# CtDPS_Stage.net
KiCad netlist of a schematic drawn in Altium Designer
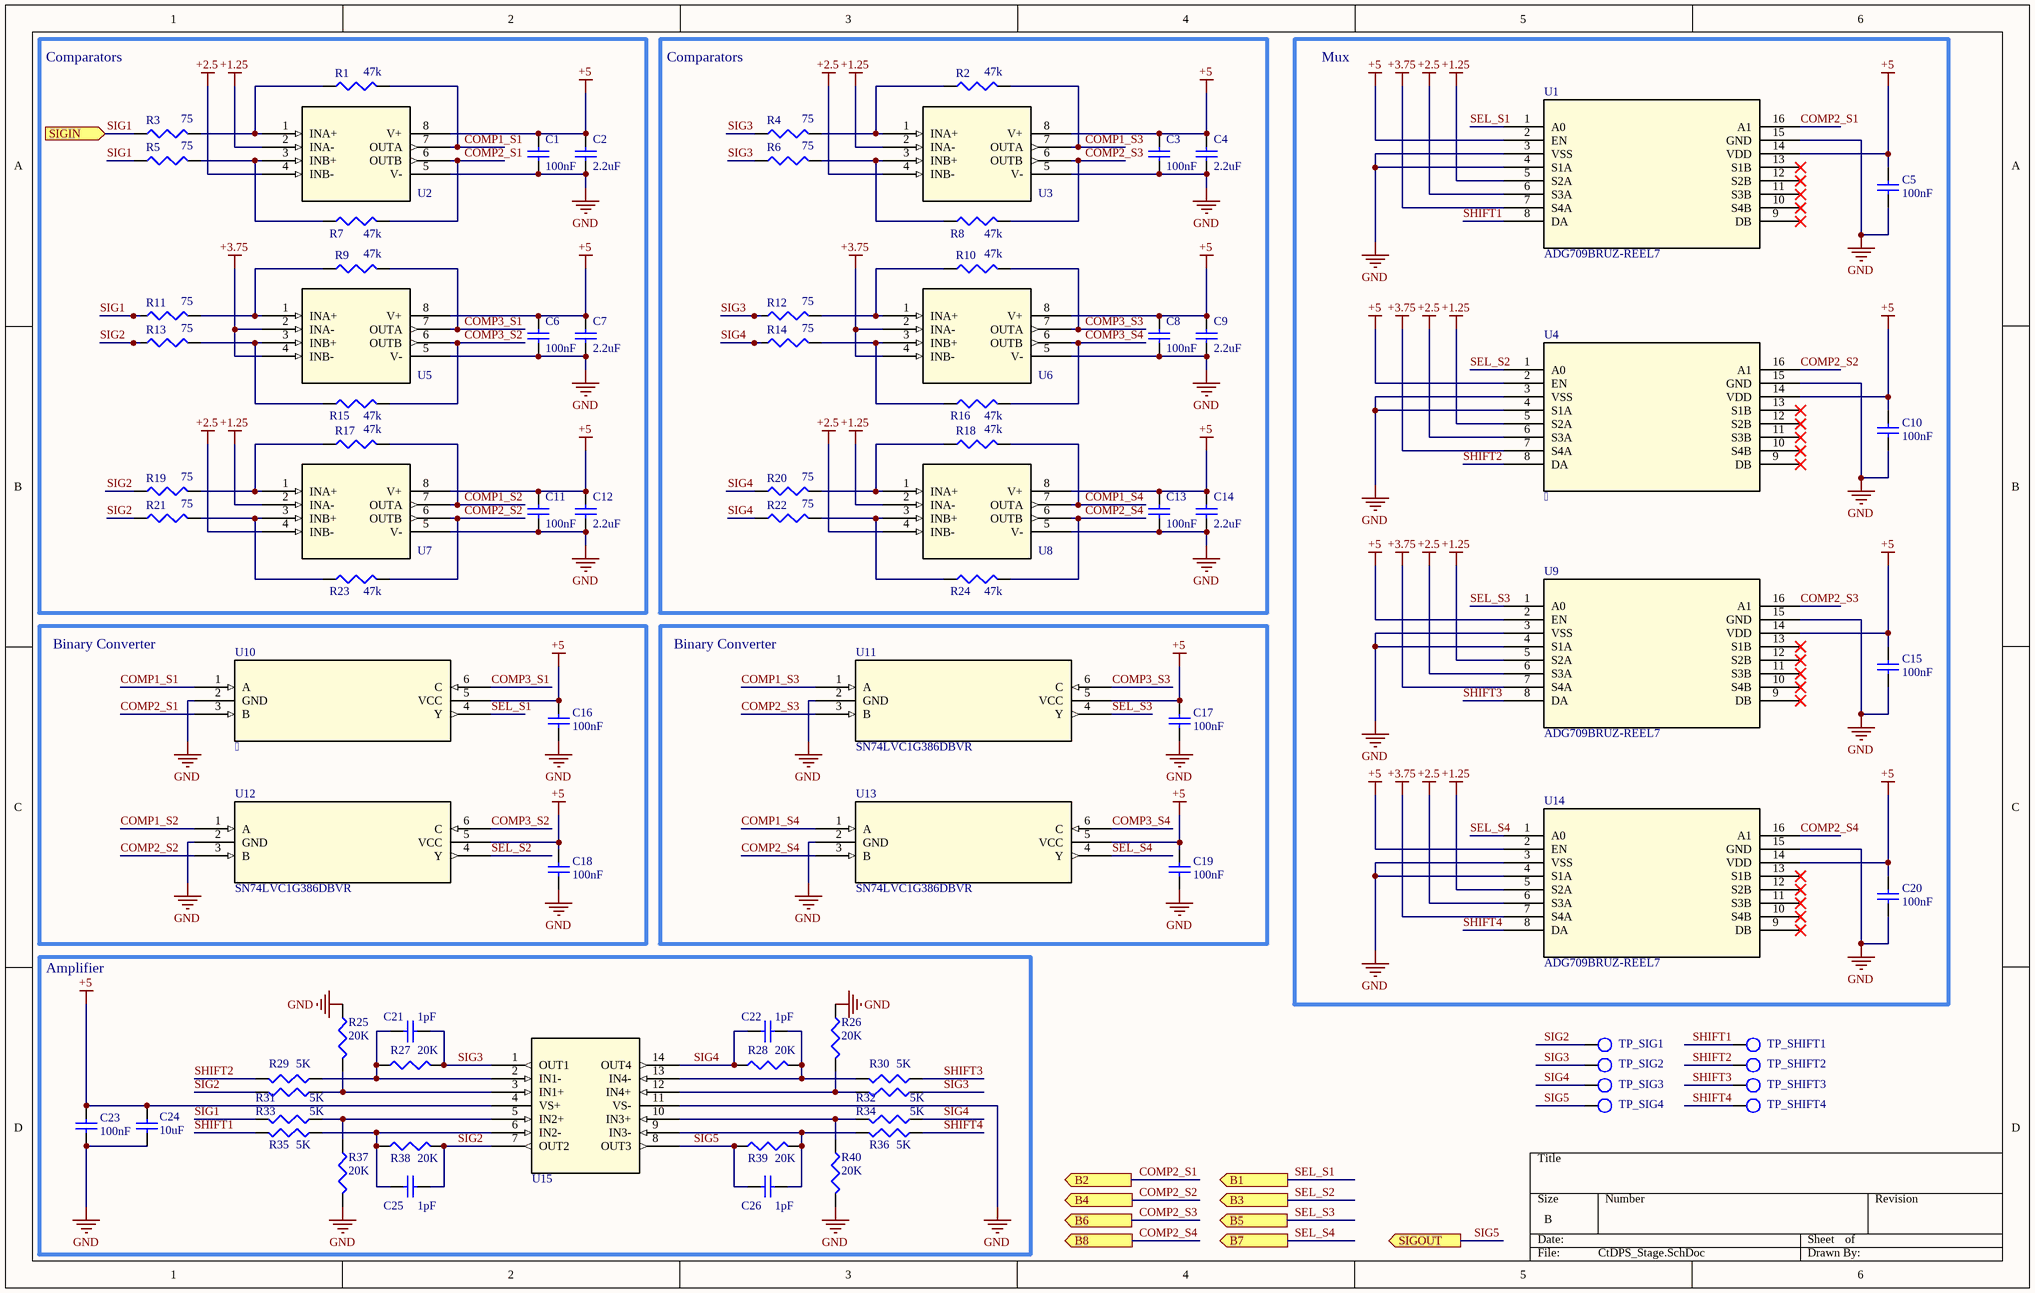
[diagram p0: CtDPS_Stage.SchDoc]

(export (version "E")
  (design (tool "Eeschema 10.0.6"))
  (components
    (comp (ref "C1")
      (value "100nF")
      (footprint "C_0402")
      (fields (field (name "LCSC PART #") "C1525"))
      (libsource (lib "ctdsp") (part "C_0402"))
    )
    (comp (ref "C2")
      (value "2.2uF")
      (footprint "C_0402")
      (fields (field (name "LCSC PART #") "C12530"))
      (libsource (lib "ctdsp") (part "C_0402"))
    )
    (comp (ref "C3")
      (value "100nF")
      (footprint "C_0402")
      (fields (field (name "LCSC PART #") "C1525"))
      (libsource (lib "ctdsp") (part "C_0402"))
    )
    (comp (ref "C4")
      (value "2.2uF")
      (footprint "C_0402")
      (fields (field (name "LCSC PART #") "C12530"))
      (libsource (lib "ctdsp") (part "C_0402"))
    )
    (comp (ref "C5")
      (value "100nF")
      (footprint "C_0402")
      (fields (field (name "LCSC PART #") "C1525"))
      (libsource (lib "ctdsp") (part "C_0402"))
    )
    (comp (ref "C6")
      (value "100nF")
      (footprint "C_0402")
      (fields (field (name "LCSC PART #") "C1525"))
      (libsource (lib "ctdsp") (part "C_0402"))
    )
    (comp (ref "C7")
      (value "2.2uF")
      (footprint "C_0402")
      (fields (field (name "LCSC PART #") "C12530"))
      (libsource (lib "ctdsp") (part "C_0402"))
    )
    (comp (ref "C8")
      (value "100nF")
      (footprint "C_0402")
      (fields (field (name "LCSC PART #") "C1525"))
      (libsource (lib "ctdsp") (part "C_0402"))
    )
    (comp (ref "C9")
      (value "2.2uF")
      (footprint "C_0402")
      (fields (field (name "LCSC PART #") "C12530"))
      (libsource (lib "ctdsp") (part "C_0402"))
    )
    (comp (ref "C10")
      (value "100nF")
      (footprint "C_0402")
      (fields (field (name "LCSC PART #") "C1525"))
      (libsource (lib "ctdsp") (part "C_0402"))
    )
    (comp (ref "C11")
      (value "100nF")
      (footprint "C_0402")
      (fields (field (name "LCSC PART #") "C1525"))
      (libsource (lib "ctdsp") (part "C_0402"))
    )
    (comp (ref "C12")
      (value "2.2uF")
      (footprint "C_0402")
      (fields (field (name "LCSC PART #") "C12530"))
      (libsource (lib "ctdsp") (part "C_0402"))
    )
    (comp (ref "C13")
      (value "100nF")
      (footprint "C_0402")
      (fields (field (name "LCSC PART #") "C1525"))
      (libsource (lib "ctdsp") (part "C_0402"))
    )
    (comp (ref "C14")
      (value "2.2uF")
      (footprint "C_0402")
      (fields (field (name "LCSC PART #") "C12530"))
      (libsource (lib "ctdsp") (part "C_0402"))
    )
    (comp (ref "C15")
      (value "100nF")
      (footprint "C_0402")
      (fields (field (name "LCSC PART #") "C1525"))
      (libsource (lib "ctdsp") (part "C_0402"))
    )
    (comp (ref "C16")
      (value "100nF")
      (footprint "C_0402")
      (fields (field (name "LCSC PART #") "C1525"))
      (libsource (lib "ctdsp") (part "C_0402"))
    )
    (comp (ref "C17")
      (value "100nF")
      (footprint "C_0402")
      (fields (field (name "LCSC PART #") "C1525"))
      (libsource (lib "ctdsp") (part "C_0402"))
    )
    (comp (ref "C18")
      (value "100nF")
      (footprint "C_0402")
      (fields (field (name "LCSC PART #") "C1525"))
      (libsource (lib "ctdsp") (part "C_0402"))
    )
    (comp (ref "C19")
      (value "100nF")
      (footprint "C_0402")
      (fields (field (name "LCSC PART #") "C1525"))
      (libsource (lib "ctdsp") (part "C_0402"))
    )
    (comp (ref "C20")
      (value "100nF")
      (footprint "C_0402")
      (fields (field (name "LCSC PART #") "C1525"))
      (libsource (lib "ctdsp") (part "C_0402"))
    )
    (comp (ref "C21")
      (value "1pF")
      (footprint "C_0402")
      (fields (field (name "LCSC PART #") "C1550"))
      (libsource (lib "ctdsp") (part "C_0402"))
    )
    (comp (ref "C22")
      (value "1pF")
      (footprint "C_0402")
      (fields (field (name "LCSC PART #") "C1550"))
      (libsource (lib "ctdsp") (part "C_0402"))
    )
    (comp (ref "C23")
      (value "100nF")
      (footprint "C_0402")
      (fields (field (name "LCSC PART #") "C1525"))
      (libsource (lib "ctdsp") (part "C_0402"))
    )
    (comp (ref "C24")
      (value "10uF")
      (footprint "C_0402")
      (fields (field (name "LCSC PART #") "C15525"))
      (libsource (lib "ctdsp") (part "C_0402"))
    )
    (comp (ref "C25")
      (value "1pF")
      (footprint "C_0402")
      (fields (field (name "LCSC PART #") "C1550"))
      (libsource (lib "ctdsp") (part "C_0402"))
    )
    (comp (ref "C26")
      (value "1pF")
      (footprint "C_0402")
      (fields (field (name "LCSC PART #") "C1550"))
      (libsource (lib "ctdsp") (part "C_0402"))
    )
    (comp (ref "R1")
      (value "47k")
      (footprint "RES_0603")
      (fields (field (name "LCSC PART #") "C25819"))
      (libsource (lib "ctdsp") (part "RES_0603"))
    )
    (comp (ref "R2")
      (value "47k")
      (footprint "RES_0603")
      (fields (field (name "LCSC PART #") "C25819"))
      (libsource (lib "ctdsp") (part "RES_0603"))
    )
    (comp (ref "R3")
      (value "75")
      (footprint "RES_0603")
      (fields (field (name "LCSC PART #") "C4275"))
      (libsource (lib "ctdsp") (part "RES_0603"))
    )
    (comp (ref "R4")
      (value "75")
      (footprint "RES_0603")
      (fields (field (name "LCSC PART #") "C4275"))
      (libsource (lib "ctdsp") (part "RES_0603"))
    )
    (comp (ref "R5")
      (value "75")
      (footprint "RES_0603")
      (fields (field (name "LCSC PART #") "C4275"))
      (libsource (lib "ctdsp") (part "RES_0603"))
    )
    (comp (ref "R6")
      (value "75")
      (footprint "RES_0603")
      (fields (field (name "LCSC PART #") "C4275"))
      (libsource (lib "ctdsp") (part "RES_0603"))
    )
    (comp (ref "R7")
      (value "47k")
      (footprint "RES_0603")
      (fields (field (name "LCSC PART #") "C25819"))
      (libsource (lib "ctdsp") (part "RES_0603"))
    )
    (comp (ref "R8")
      (value "47k")
      (footprint "RES_0603")
      (fields (field (name "LCSC PART #") "C25819"))
      (libsource (lib "ctdsp") (part "RES_0603"))
    )
    (comp (ref "R9")
      (value "47k")
      (footprint "RES_0603")
      (fields (field (name "LCSC PART #") "C25819"))
      (libsource (lib "ctdsp") (part "RES_0603"))
    )
    (comp (ref "R10")
      (value "47k")
      (footprint "RES_0603")
      (fields (field (name "LCSC PART #") "C25819"))
      (libsource (lib "ctdsp") (part "RES_0603"))
    )
    (comp (ref "R11")
      (value "75")
      (footprint "RES_0603")
      (fields (field (name "LCSC PART #") "C4275"))
      (libsource (lib "ctdsp") (part "RES_0603"))
    )
    (comp (ref "R12")
      (value "75")
      (footprint "RES_0603")
      (fields (field (name "LCSC PART #") "C4275"))
      (libsource (lib "ctdsp") (part "RES_0603"))
    )
    (comp (ref "R13")
      (value "75")
      (footprint "RES_0603")
      (fields (field (name "LCSC PART #") "C4275"))
      (libsource (lib "ctdsp") (part "RES_0603"))
    )
    (comp (ref "R14")
      (value "75")
      (footprint "RES_0603")
      (fields (field (name "LCSC PART #") "C4275"))
      (libsource (lib "ctdsp") (part "RES_0603"))
    )
    (comp (ref "R15")
      (value "47k")
      (footprint "RES_0603")
      (fields (field (name "LCSC PART #") "C25819"))
      (libsource (lib "ctdsp") (part "RES_0603"))
    )
    (comp (ref "R16")
      (value "47k")
      (footprint "RES_0603")
      (fields (field (name "LCSC PART #") "C25819"))
      (libsource (lib "ctdsp") (part "RES_0603"))
    )
    (comp (ref "R17")
      (value "47k")
      (footprint "RES_0603")
      (fields (field (name "LCSC PART #") "C25819"))
      (libsource (lib "ctdsp") (part "RES_0603"))
    )
    (comp (ref "R18")
      (value "47k")
      (footprint "RES_0603")
      (fields (field (name "LCSC PART #") "C25819"))
      (libsource (lib "ctdsp") (part "RES_0603"))
    )
    (comp (ref "R19")
      (value "75")
      (footprint "RES_0603")
      (fields (field (name "LCSC PART #") "C4275"))
      (libsource (lib "ctdsp") (part "RES_0603"))
    )
    (comp (ref "R20")
      (value "75")
      (footprint "RES_0603")
      (fields (field (name "LCSC PART #") "C4275"))
      (libsource (lib "ctdsp") (part "RES_0603"))
    )
    (comp (ref "R21")
      (value "75")
      (footprint "RES_0603")
      (fields (field (name "LCSC PART #") "C4275"))
      (libsource (lib "ctdsp") (part "RES_0603"))
    )
    (comp (ref "R22")
      (value "75")
      (footprint "RES_0603")
      (fields (field (name "LCSC PART #") "C4275"))
      (libsource (lib "ctdsp") (part "RES_0603"))
    )
    (comp (ref "R23")
      (value "47k")
      (footprint "RES_0603")
      (fields (field (name "LCSC PART #") "C25819"))
      (libsource (lib "ctdsp") (part "RES_0603"))
    )
    (comp (ref "R24")
      (value "47k")
      (footprint "RES_0603")
      (fields (field (name "LCSC PART #") "C25819"))
      (libsource (lib "ctdsp") (part "RES_0603"))
    )
    (comp (ref "R25")
      (value "20K")
      (footprint "RES_0402")
      (fields (field (name "LCSC PART #") "C25765"))
      (libsource (lib "ctdsp") (part "RES_0402"))
    )
    (comp (ref "R26")
      (value "20K")
      (footprint "RES_0402")
      (fields (field (name "LCSC PART #") "C25765"))
      (libsource (lib "ctdsp") (part "RES_0402"))
    )
    (comp (ref "R27")
      (value "20K")
      (footprint "RES_0402")
      (fields (field (name "LCSC PART #") "C25765"))
      (libsource (lib "ctdsp") (part "RES_0402"))
    )
    (comp (ref "R28")
      (value "20K")
      (footprint "RES_0402")
      (fields (field (name "LCSC PART #") "C25765"))
      (libsource (lib "ctdsp") (part "RES_0402"))
    )
    (comp (ref "R29")
      (value "5K")
      (footprint "RES_0402")
      (fields (field (name "LCSC PART #") "C5948099"))
      (libsource (lib "ctdsp") (part "RES_0402"))
    )
    (comp (ref "R30")
      (value "5K")
      (footprint "RES_0402")
      (fields (field (name "LCSC PART #") "C5948099"))
      (libsource (lib "ctdsp") (part "RES_0402"))
    )
    (comp (ref "R31")
      (value "5K")
      (footprint "RES_0402")
      (fields (field (name "LCSC PART #") "C5948099"))
      (libsource (lib "ctdsp") (part "RES_0402"))
    )
    (comp (ref "R32")
      (value "5K")
      (footprint "RES_0402")
      (fields (field (name "LCSC PART #") "C5948099"))
      (libsource (lib "ctdsp") (part "RES_0402"))
    )
    (comp (ref "R33")
      (value "5K")
      (footprint "RES_0402")
      (fields (field (name "LCSC PART #") "C5948099"))
      (libsource (lib "ctdsp") (part "RES_0402"))
    )
    (comp (ref "R34")
      (value "5K")
      (footprint "RES_0402")
      (fields (field (name "LCSC PART #") "C5948099"))
      (libsource (lib "ctdsp") (part "RES_0402"))
    )
    (comp (ref "R35")
      (value "5K")
      (footprint "RES_0402")
      (fields (field (name "LCSC PART #") "C5948099"))
      (libsource (lib "ctdsp") (part "RES_0402"))
    )
    (comp (ref "R36")
      (value "5K")
      (footprint "RES_0402")
      (fields (field (name "LCSC PART #") "C5948099"))
      (libsource (lib "ctdsp") (part "RES_0402"))
    )
    (comp (ref "R37")
      (value "20K")
      (footprint "RES_0402")
      (fields (field (name "LCSC PART #") "C25765"))
      (libsource (lib "ctdsp") (part "RES_0402"))
    )
    (comp (ref "R38")
      (value "20K")
      (footprint "RES_0402")
      (fields (field (name "LCSC PART #") "C25765"))
      (libsource (lib "ctdsp") (part "RES_0402"))
    )
    (comp (ref "R39")
      (value "20K")
      (footprint "RES_0402")
      (fields (field (name "LCSC PART #") "C25765"))
      (libsource (lib "ctdsp") (part "RES_0402"))
    )
    (comp (ref "R40")
      (value "20K")
      (footprint "RES_0402")
      (fields (field (name "LCSC PART #") "C25765"))
      (libsource (lib "ctdsp") (part "RES_0402"))
    )
    (comp (ref "TP_SHIFT1")
      (value "TESTPOINT")
      (footprint "TESTPOINT")
      (libsource (lib "ctdsp") (part "TESTPOINT"))
    )
    (comp (ref "TP_SHIFT2")
      (value "TESTPOINT")
      (footprint "TESTPOINT")
      (libsource (lib "ctdsp") (part "TESTPOINT"))
    )
    (comp (ref "TP_SHIFT3")
      (value "TESTPOINT")
      (footprint "TESTPOINT")
      (libsource (lib "ctdsp") (part "TESTPOINT"))
    )
    (comp (ref "TP_SHIFT4")
      (value "TESTPOINT")
      (footprint "TESTPOINT")
      (libsource (lib "ctdsp") (part "TESTPOINT"))
    )
    (comp (ref "TP_SIG1")
      (value "TESTPOINT")
      (footprint "TESTPOINT")
      (libsource (lib "ctdsp") (part "TESTPOINT"))
    )
    (comp (ref "TP_SIG2")
      (value "TESTPOINT")
      (footprint "TESTPOINT")
      (libsource (lib "ctdsp") (part "TESTPOINT"))
    )
    (comp (ref "TP_SIG3")
      (value "TESTPOINT")
      (footprint "TESTPOINT")
      (libsource (lib "ctdsp") (part "TESTPOINT"))
    )
    (comp (ref "TP_SIG4")
      (value "TESTPOINT")
      (footprint "TESTPOINT")
      (libsource (lib "ctdsp") (part "TESTPOINT"))
    )
    (comp (ref "U1")
      (value "ADG709BRUZ-REEL7")
      (footprint "ADG709BRUZ-REEL7")
      (description "CMOS Low Voltage, 3 Î© 4-Channel Multiplexer")
      (fields (field (name "LCSC PART #") "C206785"))
      (libsource (lib "ctdsp") (part "ADG709BRUZ-REEL7"))
    )
    (comp (ref "U2")
      (value "TLV3502AIDR")
      (footprint "TLV3502AIDR")
      (description "Dual 4.5ns Push-pull Rail-to-Rail Input, Rail-to-Rail Output TTL Comparators")
      (fields (field (name "LCSC PART #") "C131165"))
      (libsource (lib "ctdsp") (part "TLV3502AIDR"))
    )
    (comp (ref "U3")
      (value "TLV3502AIDR")
      (footprint "TLV3502AIDR")
      (description "Dual 4.5ns Push-pull Rail-to-Rail Input, Rail-to-Rail Output TTL Comparators")
      (fields (field (name "LCSC PART #") "C131165"))
      (libsource (lib "ctdsp") (part "TLV3502AIDR"))
    )
    (comp (ref "U4")
      (value "")
      (footprint "ADG709BRUZ-REEL7")
      (description "CMOS Low Voltage, 3 Î© 4-Channel Multiplexer")
      (fields (field (name "LCSC PART #") "C206785"))
      (libsource (lib "ctdsp") (part "ADG709BRUZ-REEL7"))
    )
    (comp (ref "U5")
      (value "TLV3502AIDR")
      (footprint "TLV3502AIDR")
      (description "Dual 4.5ns Push-pull Rail-to-Rail Input, Rail-to-Rail Output TTL Comparators")
      (fields (field (name "LCSC PART #") "C131165"))
      (libsource (lib "ctdsp") (part "TLV3502AIDR"))
    )
    (comp (ref "U6")
      (value "TLV3502AIDR")
      (footprint "TLV3502AIDR")
      (description "Dual 4.5ns Push-pull Rail-to-Rail Input, Rail-to-Rail Output TTL Comparators")
      (fields (field (name "LCSC PART #") "C131165"))
      (libsource (lib "ctdsp") (part "TLV3502AIDR"))
    )
    (comp (ref "U7")
      (value "TLV3502AIDR")
      (footprint "TLV3502AIDR")
      (description "Dual 4.5ns Push-pull Rail-to-Rail Input, Rail-to-Rail Output TTL Comparators")
      (fields (field (name "LCSC PART #") "C131165"))
      (libsource (lib "ctdsp") (part "TLV3502AIDR"))
    )
    (comp (ref "U8")
      (value "TLV3502AIDR")
      (footprint "TLV3502AIDR")
      (description "Dual 4.5ns Push-pull Rail-to-Rail Input, Rail-to-Rail Output TTL Comparators")
      (fields (field (name "LCSC PART #") "C131165"))
      (libsource (lib "ctdsp") (part "TLV3502AIDR"))
    )
    (comp (ref "U9")
      (value "ADG709BRUZ-REEL7")
      (footprint "ADG709BRUZ-REEL7")
      (description "CMOS Low Voltage, 3 Î© 4-Channel Multiplexer")
      (fields (field (name "LCSC PART #") "C206785"))
      (libsource (lib "ctdsp") (part "ADG709BRUZ-REEL7"))
    )
    (comp (ref "U10")
      (value "")
      (footprint "SN74LVC1G386DBVR")
      (description "Single 3-input, 1.65-V to 5.5-V XOR (exclusive OR) gate 6-SOT-23 -40 to 125")
      (fields (field (name "LCSC PART #") "C2838503"))
      (libsource (lib "ctdsp") (part "SN74LVC1G386DBVR"))
    )
    (comp (ref "U11")
      (value "SN74LVC1G386DBVR")
      (footprint "SN74LVC1G386DBVR")
      (description "Single 3-input, 1.65-V to 5.5-V XOR (exclusive OR) gate 6-SOT-23 -40 to 125")
      (fields (field (name "LCSC PART #") "C2838503"))
      (libsource (lib "ctdsp") (part "SN74LVC1G386DBVR"))
    )
    (comp (ref "U12")
      (value "SN74LVC1G386DBVR")
      (footprint "SN74LVC1G386DBVR")
      (description "Single 3-input, 1.65-V to 5.5-V XOR (exclusive OR) gate 6-SOT-23 -40 to 125")
      (fields (field (name "LCSC PART #") "C2838503"))
      (libsource (lib "ctdsp") (part "SN74LVC1G386DBVR"))
    )
    (comp (ref "U13")
      (value "SN74LVC1G386DBVR")
      (footprint "SN74LVC1G386DBVR")
      (description "Single 3-input, 1.65-V to 5.5-V XOR (exclusive OR) gate 6-SOT-23 -40 to 125")
      (fields (field (name "LCSC PART #") "C2838503"))
      (libsource (lib "ctdsp") (part "SN74LVC1G386DBVR"))
    )
    (comp (ref "U14")
      (value "ADG709BRUZ-REEL7")
      (footprint "ADG709BRUZ-REEL7")
      (description "CMOS Low Voltage, 3 Î© 4-Channel Multiplexer")
      (fields (field (name "LCSC PART #") "C206785"))
      (libsource (lib "ctdsp") (part "ADG709BRUZ-REEL7"))
    )
    (comp (ref "U15")
      (value "ADA4891-4ARZ-R7")
      (footprint "ADA4891-4ARZ-R7")
      (description "Quad Rail-to-Rail Op-Amp, 240 MHz, 170 V/µs, SOT-23-5")
      (fields (field (name "LCSC PART #") "C654290"))
      (libsource (lib "ctdsp") (part "ADA4891-4ARZ-R7"))
    )
  )
  (nets
    (net (code "1") (name "+1.25") (class "Default")
      (node (ref "U1") (pin "5") (pinfunction "S2A_5") (pintype "passive"))
      (node (ref "U14") (pin "5") (pinfunction "S2A_5") (pintype "passive"))
      (node (ref "U2") (pin "2") (pinfunction "INA-_2") (pintype "input"))
      (node (ref "U3") (pin "2") (pinfunction "INA-_2") (pintype "input"))
      (node (ref "U4") (pin "5") (pinfunction "S2A_5") (pintype "passive"))
      (node (ref "U7") (pin "2") (pinfunction "INA-_2") (pintype "input"))
      (node (ref "U8") (pin "2") (pinfunction "INA-_2") (pintype "input"))
      (node (ref "U9") (pin "5") (pinfunction "S2A_5") (pintype "passive"))
    )
    (net (code "2") (name "+2.5") (class "Default")
      (node (ref "U1") (pin "6") (pinfunction "S3A_6") (pintype "passive"))
      (node (ref "U14") (pin "6") (pinfunction "S3A_6") (pintype "passive"))
      (node (ref "U2") (pin "4") (pinfunction "INB-_4") (pintype "input"))
      (node (ref "U3") (pin "4") (pinfunction "INB-_4") (pintype "input"))
      (node (ref "U4") (pin "6") (pinfunction "S3A_6") (pintype "passive"))
      (node (ref "U7") (pin "4") (pinfunction "INB-_4") (pintype "input"))
      (node (ref "U8") (pin "4") (pinfunction "INB-_4") (pintype "input"))
      (node (ref "U9") (pin "6") (pinfunction "S3A_6") (pintype "passive"))
    )
    (net (code "3") (name "+3.75") (class "Default")
      (node (ref "U1") (pin "7") (pinfunction "S4A_7") (pintype "passive"))
      (node (ref "U14") (pin "7") (pinfunction "S4A_7") (pintype "passive"))
      (node (ref "U4") (pin "7") (pinfunction "S4A_7") (pintype "passive"))
      (node (ref "U5") (pin "2") (pinfunction "INA-_2") (pintype "input"))
      (node (ref "U5") (pin "4") (pinfunction "INB-_4") (pintype "input"))
      (node (ref "U6") (pin "2") (pinfunction "INA-_2") (pintype "input"))
      (node (ref "U6") (pin "4") (pinfunction "INB-_4") (pintype "input"))
      (node (ref "U9") (pin "7") (pinfunction "S4A_7") (pintype "passive"))
    )
    (net (code "4") (name "+5") (class "Default")
      (node (ref "C1") (pin "1") (pinfunction "1_1") (pintype "passive"))
      (node (ref "C10") (pin "1") (pinfunction "1_1") (pintype "passive"))
      (node (ref "C11") (pin "1") (pinfunction "1_1") (pintype "passive"))
      (node (ref "C12") (pin "2") (pinfunction "2_2") (pintype "passive"))
      (node (ref "C13") (pin "1") (pinfunction "1_1") (pintype "passive"))
      (node (ref "C14") (pin "2") (pinfunction "2_2") (pintype "passive"))
      (node (ref "C15") (pin "1") (pinfunction "1_1") (pintype "passive"))
      (node (ref "C16") (pin "1") (pinfunction "1_1") (pintype "passive"))
      (node (ref "C17") (pin "1") (pinfunction "1_1") (pintype "passive"))
      (node (ref "C18") (pin "1") (pinfunction "1_1") (pintype "passive"))
      (node (ref "C19") (pin "1") (pinfunction "1_1") (pintype "passive"))
      (node (ref "C2") (pin "2") (pinfunction "2_2") (pintype "passive"))
      (node (ref "C20") (pin "1") (pinfunction "1_1") (pintype "passive"))
      (node (ref "C23") (pin "1") (pinfunction "1_1") (pintype "passive"))
      (node (ref "C24") (pin "2") (pinfunction "2_2") (pintype "passive"))
      (node (ref "C3") (pin "1") (pinfunction "1_1") (pintype "passive"))
      (node (ref "C4") (pin "2") (pinfunction "2_2") (pintype "passive"))
      (node (ref "C5") (pin "1") (pinfunction "1_1") (pintype "passive"))
      (node (ref "C6") (pin "1") (pinfunction "1_1") (pintype "passive"))
      (node (ref "C7") (pin "2") (pinfunction "2_2") (pintype "passive"))
      (node (ref "C8") (pin "1") (pinfunction "1_1") (pintype "passive"))
      (node (ref "C9") (pin "2") (pinfunction "2_2") (pintype "passive"))
      (node (ref "U1") (pin "14") (pinfunction "VDD_14") (pintype "power_in"))
      (node (ref "U1") (pin "2") (pinfunction "EN_2") (pintype "passive"))
      (node (ref "U10") (pin "5") (pinfunction "VCC_5") (pintype "power_in"))
      (node (ref "U11") (pin "5") (pinfunction "VCC_5") (pintype "power_in"))
      (node (ref "U12") (pin "5") (pinfunction "VCC_5") (pintype "power_in"))
      (node (ref "U13") (pin "5") (pinfunction "VCC_5") (pintype "power_in"))
      (node (ref "U14") (pin "14") (pinfunction "VDD_14") (pintype "power_in"))
      (node (ref "U14") (pin "2") (pinfunction "EN_2") (pintype "passive"))
      (node (ref "U15") (pin "4") (pinfunction "VS+_4") (pintype "power_in"))
      (node (ref "U2") (pin "8") (pinfunction "V+_8") (pintype "power_in"))
      (node (ref "U3") (pin "8") (pinfunction "V+_8") (pintype "power_in"))
      (node (ref "U4") (pin "14") (pinfunction "VDD_14") (pintype "power_in"))
      (node (ref "U4") (pin "2") (pinfunction "EN_2") (pintype "passive"))
      (node (ref "U5") (pin "8") (pinfunction "V+_8") (pintype "power_in"))
      (node (ref "U6") (pin "8") (pinfunction "V+_8") (pintype "power_in"))
      (node (ref "U7") (pin "8") (pinfunction "V+_8") (pintype "power_in"))
      (node (ref "U8") (pin "8") (pinfunction "V+_8") (pintype "power_in"))
      (node (ref "U9") (pin "14") (pinfunction "VDD_14") (pintype "power_in"))
      (node (ref "U9") (pin "2") (pinfunction "EN_2") (pintype "passive"))
    )
    (net (code "5") (name "/COMP1_S1") (class "Default")
      (node (ref "R1") (pin "2") (pinfunction "2_2") (pintype "passive"))
      (node (ref "U10") (pin "1") (pinfunction "A_1") (pintype "input"))
      (node (ref "U2") (pin "7") (pinfunction "OUTA_7") (pintype "output"))
    )
    (net (code "6") (name "/COMP1_S2") (class "Default")
      (node (ref "R17") (pin "2") (pinfunction "2_2") (pintype "passive"))
      (node (ref "U12") (pin "1") (pinfunction "A_1") (pintype "input"))
      (node (ref "U7") (pin "7") (pinfunction "OUTA_7") (pintype "output"))
    )
    (net (code "7") (name "/COMP1_S3") (class "Default")
      (node (ref "R2") (pin "2") (pinfunction "2_2") (pintype "passive"))
      (node (ref "U11") (pin "1") (pinfunction "A_1") (pintype "input"))
      (node (ref "U3") (pin "7") (pinfunction "OUTA_7") (pintype "output"))
    )
    (net (code "8") (name "/COMP1_S4") (class "Default")
      (node (ref "R18") (pin "2") (pinfunction "2_2") (pintype "passive"))
      (node (ref "U13") (pin "1") (pinfunction "A_1") (pintype "input"))
      (node (ref "U8") (pin "7") (pinfunction "OUTA_7") (pintype "output"))
    )
    (net (code "9") (name "/COMP2_S1") (class "Default")
      (node (ref "R7") (pin "2") (pinfunction "2_2") (pintype "passive"))
      (node (ref "U1") (pin "16") (pinfunction "A1_16") (pintype "passive"))
      (node (ref "U10") (pin "3") (pinfunction "B_3") (pintype "input"))
      (node (ref "U2") (pin "6") (pinfunction "OUTB_6") (pintype "output"))
    )
    (net (code "10") (name "/COMP2_S2") (class "Default")
      (node (ref "R23") (pin "2") (pinfunction "2_2") (pintype "passive"))
      (node (ref "U12") (pin "3") (pinfunction "B_3") (pintype "input"))
      (node (ref "U4") (pin "16") (pinfunction "A1_16") (pintype "passive"))
      (node (ref "U7") (pin "6") (pinfunction "OUTB_6") (pintype "output"))
    )
    (net (code "11") (name "/COMP2_S3") (class "Default")
      (node (ref "R8") (pin "2") (pinfunction "2_2") (pintype "passive"))
      (node (ref "U11") (pin "3") (pinfunction "B_3") (pintype "input"))
      (node (ref "U3") (pin "6") (pinfunction "OUTB_6") (pintype "output"))
      (node (ref "U9") (pin "16") (pinfunction "A1_16") (pintype "passive"))
    )
    (net (code "12") (name "/COMP2_S4") (class "Default")
      (node (ref "R24") (pin "2") (pinfunction "2_2") (pintype "passive"))
      (node (ref "U13") (pin "3") (pinfunction "B_3") (pintype "input"))
      (node (ref "U14") (pin "16") (pinfunction "A1_16") (pintype "passive"))
      (node (ref "U8") (pin "6") (pinfunction "OUTB_6") (pintype "output"))
    )
    (net (code "13") (name "/COMP3_S1") (class "Default")
      (node (ref "R9") (pin "2") (pinfunction "2_2") (pintype "passive"))
      (node (ref "U10") (pin "6") (pinfunction "C_6") (pintype "input"))
      (node (ref "U5") (pin "7") (pinfunction "OUTA_7") (pintype "output"))
    )
    (net (code "14") (name "/COMP3_S2") (class "Default")
      (node (ref "R15") (pin "2") (pinfunction "2_2") (pintype "passive"))
      (node (ref "U12") (pin "6") (pinfunction "C_6") (pintype "input"))
      (node (ref "U5") (pin "6") (pinfunction "OUTB_6") (pintype "output"))
    )
    (net (code "15") (name "/COMP3_S3") (class "Default")
      (node (ref "R10") (pin "2") (pinfunction "2_2") (pintype "passive"))
      (node (ref "U11") (pin "6") (pinfunction "C_6") (pintype "input"))
      (node (ref "U6") (pin "7") (pinfunction "OUTA_7") (pintype "output"))
    )
    (net (code "16") (name "/COMP3_S4") (class "Default")
      (node (ref "R16") (pin "2") (pinfunction "2_2") (pintype "passive"))
      (node (ref "U13") (pin "6") (pinfunction "C_6") (pintype "input"))
      (node (ref "U6") (pin "6") (pinfunction "OUTB_6") (pintype "output"))
    )
    (net (code "17") (name "/SEL_S1") (class "Default")
      (node (ref "U1") (pin "1") (pinfunction "A0_1") (pintype "passive"))
      (node (ref "U10") (pin "4") (pinfunction "Y_4") (pintype "output"))
    )
    (net (code "18") (name "/SEL_S2") (class "Default")
      (node (ref "U12") (pin "4") (pinfunction "Y_4") (pintype "output"))
      (node (ref "U4") (pin "1") (pinfunction "A0_1") (pintype "passive"))
    )
    (net (code "19") (name "/SEL_S3") (class "Default")
      (node (ref "U11") (pin "4") (pinfunction "Y_4") (pintype "output"))
      (node (ref "U9") (pin "1") (pinfunction "A0_1") (pintype "passive"))
    )
    (net (code "20") (name "/SEL_S4") (class "Default")
      (node (ref "U13") (pin "4") (pinfunction "Y_4") (pintype "output"))
      (node (ref "U14") (pin "1") (pinfunction "A0_1") (pintype "passive"))
    )
    (net (code "21") (name "/SHIFT1") (class "Default")
      (node (ref "R35") (pin "1") (pinfunction "1_1") (pintype "passive"))
      (node (ref "TP_SHIFT1") (pin "1") (pinfunction "1_1") (pintype "passive"))
      (node (ref "U1") (pin "8") (pinfunction "DA_8") (pintype "passive"))
    )
    (net (code "22") (name "/SHIFT2") (class "Default")
      (node (ref "R29") (pin "1") (pinfunction "1_1") (pintype "passive"))
      (node (ref "TP_SHIFT2") (pin "1") (pinfunction "1_1") (pintype "passive"))
      (node (ref "U4") (pin "8") (pinfunction "DA_8") (pintype "passive"))
    )
    (net (code "23") (name "/SHIFT3") (class "Default")
      (node (ref "R30") (pin "2") (pinfunction "2_2") (pintype "passive"))
      (node (ref "TP_SHIFT3") (pin "1") (pinfunction "1_1") (pintype "passive"))
      (node (ref "U9") (pin "8") (pinfunction "DA_8") (pintype "passive"))
    )
    (net (code "24") (name "/SHIFT4") (class "Default")
      (node (ref "R36") (pin "2") (pinfunction "2_2") (pintype "passive"))
      (node (ref "TP_SHIFT4") (pin "1") (pinfunction "1_1") (pintype "passive"))
      (node (ref "U14") (pin "8") (pinfunction "DA_8") (pintype "passive"))
    )
    (net (code "25") (name "/SIG1") (class "Default")
      (node (ref "R11") (pin "1") (pinfunction "1_1") (pintype "passive"))
      (node (ref "R3") (pin "1") (pinfunction "1_1") (pintype "passive"))
      (node (ref "R33") (pin "1") (pinfunction "1_1") (pintype "passive"))
      (node (ref "R5") (pin "1") (pinfunction "1_1") (pintype "passive"))
    )
    (net (code "26") (name "/SIG2") (class "Default")
      (node (ref "C25") (pin "2") (pinfunction "2_2") (pintype "passive"))
      (node (ref "R13") (pin "1") (pinfunction "1_1") (pintype "passive"))
      (node (ref "R19") (pin "1") (pinfunction "1_1") (pintype "passive"))
      (node (ref "R21") (pin "1") (pinfunction "1_1") (pintype "passive"))
      (node (ref "R31") (pin "1") (pinfunction "1_1") (pintype "passive"))
      (node (ref "R38") (pin "2") (pinfunction "2_2") (pintype "passive"))
      (node (ref "TP_SIG1") (pin "1") (pinfunction "1_1") (pintype "passive"))
      (node (ref "U15") (pin "7") (pinfunction "OUT2_7") (pintype "output"))
    )
    (net (code "27") (name "/SIG3") (class "Default")
      (node (ref "C21") (pin "2") (pinfunction "2_2") (pintype "passive"))
      (node (ref "R12") (pin "1") (pinfunction "1_1") (pintype "passive"))
      (node (ref "R27") (pin "2") (pinfunction "2_2") (pintype "passive"))
      (node (ref "R32") (pin "2") (pinfunction "2_2") (pintype "passive"))
      (node (ref "R4") (pin "1") (pinfunction "1_1") (pintype "passive"))
      (node (ref "R6") (pin "1") (pinfunction "1_1") (pintype "passive"))
      (node (ref "TP_SIG2") (pin "1") (pinfunction "1_1") (pintype "passive"))
      (node (ref "U15") (pin "1") (pinfunction "OUT1_1") (pintype "output"))
    )
    (net (code "28") (name "/SIG4") (class "Default")
      (node (ref "C22") (pin "1") (pinfunction "1_1") (pintype "passive"))
      (node (ref "R14") (pin "1") (pinfunction "1_1") (pintype "passive"))
      (node (ref "R20") (pin "1") (pinfunction "1_1") (pintype "passive"))
      (node (ref "R22") (pin "1") (pinfunction "1_1") (pintype "passive"))
      (node (ref "R28") (pin "1") (pinfunction "1_1") (pintype "passive"))
      (node (ref "R34") (pin "2") (pinfunction "2_2") (pintype "passive"))
      (node (ref "TP_SIG3") (pin "1") (pinfunction "1_1") (pintype "passive"))
      (node (ref "U15") (pin "14") (pinfunction "OUT4_14") (pintype "output"))
    )
    (net (code "29") (name "/SIG5") (class "Default")
      (node (ref "C26") (pin "1") (pinfunction "1_1") (pintype "passive"))
      (node (ref "R39") (pin "1") (pinfunction "1_1") (pintype "passive"))
      (node (ref "TP_SIG4") (pin "1") (pinfunction "1_1") (pintype "passive"))
      (node (ref "U15") (pin "8") (pinfunction "OUT3_8") (pintype "output"))
    )
    (net (code "30") (name "GND") (class "Default")
      (node (ref "C1") (pin "2") (pinfunction "2_2") (pintype "passive"))
      (node (ref "C10") (pin "2") (pinfunction "2_2") (pintype "passive"))
      (node (ref "C11") (pin "2") (pinfunction "2_2") (pintype "passive"))
      (node (ref "C12") (pin "1") (pinfunction "1_1") (pintype "passive"))
      (node (ref "C13") (pin "2") (pinfunction "2_2") (pintype "passive"))
      (node (ref "C14") (pin "1") (pinfunction "1_1") (pintype "passive"))
      (node (ref "C15") (pin "2") (pinfunction "2_2") (pintype "passive"))
      (node (ref "C16") (pin "2") (pinfunction "2_2") (pintype "passive"))
      (node (ref "C17") (pin "2") (pinfunction "2_2") (pintype "passive"))
      (node (ref "C18") (pin "2") (pinfunction "2_2") (pintype "passive"))
      (node (ref "C19") (pin "2") (pinfunction "2_2") (pintype "passive"))
      (node (ref "C2") (pin "1") (pinfunction "1_1") (pintype "passive"))
      (node (ref "C20") (pin "2") (pinfunction "2_2") (pintype "passive"))
      (node (ref "C23") (pin "2") (pinfunction "2_2") (pintype "passive"))
      (node (ref "C24") (pin "1") (pinfunction "1_1") (pintype "passive"))
      (node (ref "C3") (pin "2") (pinfunction "2_2") (pintype "passive"))
      (node (ref "C4") (pin "1") (pinfunction "1_1") (pintype "passive"))
      (node (ref "C5") (pin "2") (pinfunction "2_2") (pintype "passive"))
      (node (ref "C6") (pin "2") (pinfunction "2_2") (pintype "passive"))
      (node (ref "C7") (pin "1") (pinfunction "1_1") (pintype "passive"))
      (node (ref "C8") (pin "2") (pinfunction "2_2") (pintype "passive"))
      (node (ref "C9") (pin "1") (pinfunction "1_1") (pintype "passive"))
      (node (ref "R25") (pin "1") (pinfunction "1_1") (pintype "passive"))
      (node (ref "R26") (pin "1") (pinfunction "1_1") (pintype "passive"))
      (node (ref "R37") (pin "2") (pinfunction "2_2") (pintype "passive"))
      (node (ref "R40") (pin "2") (pinfunction "2_2") (pintype "passive"))
      (node (ref "U1") (pin "15") (pinfunction "GND_15") (pintype "passive"))
      (node (ref "U1") (pin "3") (pinfunction "VSS_3") (pintype "power_in"))
      (node (ref "U1") (pin "4") (pinfunction "S1A_4") (pintype "passive"))
      (node (ref "U10") (pin "2") (pinfunction "GND_2") (pintype "power_in"))
      (node (ref "U11") (pin "2") (pinfunction "GND_2") (pintype "power_in"))
      (node (ref "U12") (pin "2") (pinfunction "GND_2") (pintype "power_in"))
      (node (ref "U13") (pin "2") (pinfunction "GND_2") (pintype "power_in"))
      (node (ref "U14") (pin "15") (pinfunction "GND_15") (pintype "passive"))
      (node (ref "U14") (pin "3") (pinfunction "VSS_3") (pintype "power_in"))
      (node (ref "U14") (pin "4") (pinfunction "S1A_4") (pintype "passive"))
      (node (ref "U15") (pin "11") (pinfunction "VS-_11") (pintype "power_in"))
      (node (ref "U2") (pin "5") (pinfunction "V-_5") (pintype "power_in"))
      (node (ref "U3") (pin "5") (pinfunction "V-_5") (pintype "power_in"))
      (node (ref "U4") (pin "15") (pinfunction "GND_15") (pintype "passive"))
      (node (ref "U4") (pin "3") (pinfunction "VSS_3") (pintype "power_in"))
      (node (ref "U4") (pin "4") (pinfunction "S1A_4") (pintype "passive"))
      (node (ref "U5") (pin "5") (pinfunction "V-_5") (pintype "power_in"))
      (node (ref "U6") (pin "5") (pinfunction "V-_5") (pintype "power_in"))
      (node (ref "U7") (pin "5") (pinfunction "V-_5") (pintype "power_in"))
      (node (ref "U8") (pin "5") (pinfunction "V-_5") (pintype "power_in"))
      (node (ref "U9") (pin "15") (pinfunction "GND_15") (pintype "passive"))
      (node (ref "U9") (pin "3") (pinfunction "VSS_3") (pintype "power_in"))
      (node (ref "U9") (pin "4") (pinfunction "S1A_4") (pintype "passive"))
    )
    (net (code "31") (name "Net-(U2-INA+)") (class "Default")
      (node (ref "R1") (pin "1") (pinfunction "1_1") (pintype "passive"))
      (node (ref "R3") (pin "2") (pinfunction "2_2") (pintype "passive"))
      (node (ref "U2") (pin "1") (pinfunction "INA+_1") (pintype "input"))
    )
    (net (code "32") (name "Net-(U2-INB+)") (class "Default")
      (node (ref "R5") (pin "2") (pinfunction "2_2") (pintype "passive"))
      (node (ref "R7") (pin "1") (pinfunction "1_1") (pintype "passive"))
      (node (ref "U2") (pin "3") (pinfunction "INB+_3") (pintype "input"))
    )
    (net (code "33") (name "Net-(U3-INA+)") (class "Default")
      (node (ref "R2") (pin "1") (pinfunction "1_1") (pintype "passive"))
      (node (ref "R4") (pin "2") (pinfunction "2_2") (pintype "passive"))
      (node (ref "U3") (pin "1") (pinfunction "INA+_1") (pintype "input"))
    )
    (net (code "34") (name "Net-(U3-INB+)") (class "Default")
      (node (ref "R6") (pin "2") (pinfunction "2_2") (pintype "passive"))
      (node (ref "R8") (pin "1") (pinfunction "1_1") (pintype "passive"))
      (node (ref "U3") (pin "3") (pinfunction "INB+_3") (pintype "input"))
    )
    (net (code "35") (name "Net-(U5-INA+)") (class "Default")
      (node (ref "R11") (pin "2") (pinfunction "2_2") (pintype "passive"))
      (node (ref "R9") (pin "1") (pinfunction "1_1") (pintype "passive"))
      (node (ref "U5") (pin "1") (pinfunction "INA+_1") (pintype "input"))
    )
    (net (code "36") (name "Net-(U5-INB+)") (class "Default")
      (node (ref "R13") (pin "2") (pinfunction "2_2") (pintype "passive"))
      (node (ref "R15") (pin "1") (pinfunction "1_1") (pintype "passive"))
      (node (ref "U5") (pin "3") (pinfunction "INB+_3") (pintype "input"))
    )
    (net (code "37") (name "Net-(U6-INA+)") (class "Default")
      (node (ref "R10") (pin "1") (pinfunction "1_1") (pintype "passive"))
      (node (ref "R12") (pin "2") (pinfunction "2_2") (pintype "passive"))
      (node (ref "U6") (pin "1") (pinfunction "INA+_1") (pintype "input"))
    )
    (net (code "38") (name "Net-(U6-INB+)") (class "Default")
      (node (ref "R14") (pin "2") (pinfunction "2_2") (pintype "passive"))
      (node (ref "R16") (pin "1") (pinfunction "1_1") (pintype "passive"))
      (node (ref "U6") (pin "3") (pinfunction "INB+_3") (pintype "input"))
    )
    (net (code "39") (name "Net-(U7-INA+)") (class "Default")
      (node (ref "R17") (pin "1") (pinfunction "1_1") (pintype "passive"))
      (node (ref "R19") (pin "2") (pinfunction "2_2") (pintype "passive"))
      (node (ref "U7") (pin "1") (pinfunction "INA+_1") (pintype "input"))
    )
    (net (code "40") (name "Net-(U7-INB+)") (class "Default")
      (node (ref "R21") (pin "2") (pinfunction "2_2") (pintype "passive"))
      (node (ref "R23") (pin "1") (pinfunction "1_1") (pintype "passive"))
      (node (ref "U7") (pin "3") (pinfunction "INB+_3") (pintype "input"))
    )
    (net (code "41") (name "Net-(U8-INA+)") (class "Default")
      (node (ref "R18") (pin "1") (pinfunction "1_1") (pintype "passive"))
      (node (ref "R20") (pin "2") (pinfunction "2_2") (pintype "passive"))
      (node (ref "U8") (pin "1") (pinfunction "INA+_1") (pintype "input"))
    )
    (net (code "42") (name "Net-(U8-INB+)") (class "Default")
      (node (ref "R22") (pin "2") (pinfunction "2_2") (pintype "passive"))
      (node (ref "R24") (pin "1") (pinfunction "1_1") (pintype "passive"))
      (node (ref "U8") (pin "3") (pinfunction "INB+_3") (pintype "input"))
    )
    (net (code "43") (name "Net-(U15-IN1+)") (class "Default")
      (node (ref "R25") (pin "2") (pinfunction "2_2") (pintype "passive"))
      (node (ref "R31") (pin "2") (pinfunction "2_2") (pintype "passive"))
      (node (ref "U15") (pin "3") (pinfunction "IN1+_3") (pintype "input"))
    )
    (net (code "44") (name "Net-(U15-IN1-)") (class "Default")
      (node (ref "C21") (pin "1") (pinfunction "1_1") (pintype "passive"))
      (node (ref "R27") (pin "1") (pinfunction "1_1") (pintype "passive"))
      (node (ref "R29") (pin "2") (pinfunction "2_2") (pintype "passive"))
      (node (ref "U15") (pin "2") (pinfunction "IN1-_2") (pintype "input"))
    )
    (net (code "45") (name "Net-(U15-IN2+)") (class "Default")
      (node (ref "R33") (pin "2") (pinfunction "2_2") (pintype "passive"))
      (node (ref "R37") (pin "1") (pinfunction "1_1") (pintype "passive"))
      (node (ref "U15") (pin "5") (pinfunction "IN2+_5") (pintype "input"))
    )
    (net (code "46") (name "Net-(U15-IN2-)") (class "Default")
      (node (ref "C25") (pin "1") (pinfunction "1_1") (pintype "passive"))
      (node (ref "R35") (pin "2") (pinfunction "2_2") (pintype "passive"))
      (node (ref "R38") (pin "1") (pinfunction "1_1") (pintype "passive"))
      (node (ref "U15") (pin "6") (pinfunction "IN2-_6") (pintype "input"))
    )
    (net (code "47") (name "Net-(U15-IN3+)") (class "Default")
      (node (ref "R34") (pin "1") (pinfunction "1_1") (pintype "passive"))
      (node (ref "R40") (pin "1") (pinfunction "1_1") (pintype "passive"))
      (node (ref "U15") (pin "10") (pinfunction "IN3+_10") (pintype "input"))
    )
    (net (code "48") (name "Net-(U15-IN3-)") (class "Default")
      (node (ref "C26") (pin "2") (pinfunction "2_2") (pintype "passive"))
      (node (ref "R36") (pin "1") (pinfunction "1_1") (pintype "passive"))
      (node (ref "R39") (pin "2") (pinfunction "2_2") (pintype "passive"))
      (node (ref "U15") (pin "9") (pinfunction "IN3-_9") (pintype "input"))
    )
    (net (code "49") (name "Net-(U15-IN4+)") (class "Default")
      (node (ref "R26") (pin "2") (pinfunction "2_2") (pintype "passive"))
      (node (ref "R32") (pin "1") (pinfunction "1_1") (pintype "passive"))
      (node (ref "U15") (pin "12") (pinfunction "IN4+_12") (pintype "input"))
    )
    (net (code "50") (name "Net-(U15-IN4-)") (class "Default")
      (node (ref "C22") (pin "2") (pinfunction "2_2") (pintype "passive"))
      (node (ref "R28") (pin "2") (pinfunction "2_2") (pintype "passive"))
      (node (ref "R30") (pin "1") (pinfunction "1_1") (pintype "passive"))
      (node (ref "U15") (pin "13") (pinfunction "IN4-_13") (pintype "input"))
    )
    (net (code "51") (name "unconnected-(U1-DB-Pad9)") (class "Default")
      (node (ref "U1") (pin "9") (pinfunction "DB_9") (pintype "passive+no_connect"))
    )
    (net (code "52") (name "unconnected-(U1-S1B-Pad13)") (class "Default")
      (node (ref "U1") (pin "13") (pinfunction "S1B_13") (pintype "passive+no_connect"))
    )
    (net (code "53") (name "unconnected-(U1-S2B-Pad12)") (class "Default")
      (node (ref "U1") (pin "12") (pinfunction "S2B_12") (pintype "passive+no_connect"))
    )
    (net (code "54") (name "unconnected-(U1-S3B-Pad11)") (class "Default")
      (node (ref "U1") (pin "11") (pinfunction "S3B_11") (pintype "passive+no_connect"))
    )
    (net (code "55") (name "unconnected-(U1-S4B-Pad10)") (class "Default")
      (node (ref "U1") (pin "10") (pinfunction "S4B_10") (pintype "passive+no_connect"))
    )
    (net (code "56") (name "unconnected-(U4-DB-Pad9)") (class "Default")
      (node (ref "U4") (pin "9") (pinfunction "DB_9") (pintype "passive+no_connect"))
    )
    (net (code "57") (name "unconnected-(U4-S1B-Pad13)") (class "Default")
      (node (ref "U4") (pin "13") (pinfunction "S1B_13") (pintype "passive+no_connect"))
    )
    (net (code "58") (name "unconnected-(U4-S2B-Pad12)") (class "Default")
      (node (ref "U4") (pin "12") (pinfunction "S2B_12") (pintype "passive+no_connect"))
    )
    (net (code "59") (name "unconnected-(U4-S3B-Pad11)") (class "Default")
      (node (ref "U4") (pin "11") (pinfunction "S3B_11") (pintype "passive+no_connect"))
    )
    (net (code "60") (name "unconnected-(U4-S4B-Pad10)") (class "Default")
      (node (ref "U4") (pin "10") (pinfunction "S4B_10") (pintype "passive+no_connect"))
    )
    (net (code "61") (name "unconnected-(U9-DB-Pad9)") (class "Default")
      (node (ref "U9") (pin "9") (pinfunction "DB_9") (pintype "passive+no_connect"))
    )
    (net (code "62") (name "unconnected-(U9-S1B-Pad13)") (class "Default")
      (node (ref "U9") (pin "13") (pinfunction "S1B_13") (pintype "passive+no_connect"))
    )
    (net (code "63") (name "unconnected-(U9-S2B-Pad12)") (class "Default")
      (node (ref "U9") (pin "12") (pinfunction "S2B_12") (pintype "passive+no_connect"))
    )
    (net (code "64") (name "unconnected-(U9-S3B-Pad11)") (class "Default")
      (node (ref "U9") (pin "11") (pinfunction "S3B_11") (pintype "passive+no_connect"))
    )
    (net (code "65") (name "unconnected-(U9-S4B-Pad10)") (class "Default")
      (node (ref "U9") (pin "10") (pinfunction "S4B_10") (pintype "passive+no_connect"))
    )
    (net (code "66") (name "unconnected-(U14-DB-Pad9)") (class "Default")
      (node (ref "U14") (pin "9") (pinfunction "DB_9") (pintype "passive+no_connect"))
    )
    (net (code "67") (name "unconnected-(U14-S1B-Pad13)") (class "Default")
      (node (ref "U14") (pin "13") (pinfunction "S1B_13") (pintype "passive+no_connect"))
    )
    (net (code "68") (name "unconnected-(U14-S2B-Pad12)") (class "Default")
      (node (ref "U14") (pin "12") (pinfunction "S2B_12") (pintype "passive+no_connect"))
    )
    (net (code "69") (name "unconnected-(U14-S3B-Pad11)") (class "Default")
      (node (ref "U14") (pin "11") (pinfunction "S3B_11") (pintype "passive+no_connect"))
    )
    (net (code "70") (name "unconnected-(U14-S4B-Pad10)") (class "Default")
      (node (ref "U14") (pin "10") (pinfunction "S4B_10") (pintype "passive+no_connect"))
    )
  )
)
